# USB.net
KiCad netlist of a schematic drawn in Altium Designer
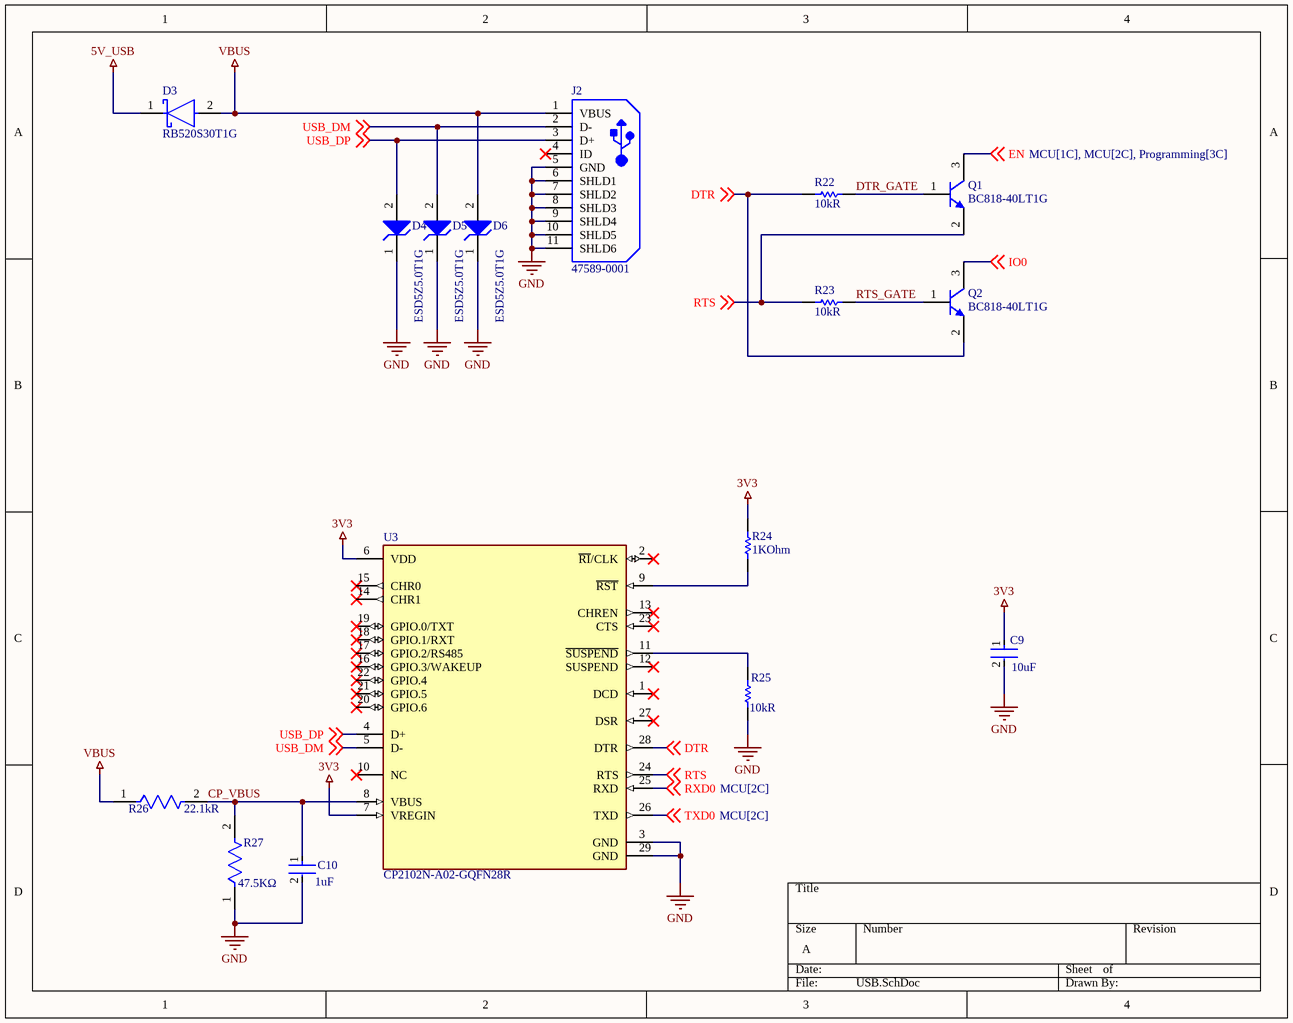
[diagram p0: USB.SchDoc]

(export (version "E")
  (design (tool "Eeschema 10.0.6"))
  (components
    (comp (ref "C9")
      (value "10uF")
      (footprint "FP-C0805C-DG-MFG")
      (description "CAP CER 10UF 10V X5R 0805")
      (fields (field (name "TOLERANCE") "10%") (field (name "MANUFACTURER PART NUMBER") "C0805C106K8PACTU"))
      (libsource (lib "Altium Content Vault") (part "11868f565c42a9108669ba33697ecf6"))
    )
    (comp (ref "C10")
      (value "CL21B105KOFNNNE")
      (footprint "FP-CL21-IPC_A")
      (description "CL21 Series 0805 1uF 16V ±10% Tolerance X7R Multilayer Ceramic Chip Capacitor")
      (fields
        (field (name "CAPACITANCE") "1uF")
        (field (name "TOLERANCE") "10%")
        (field (name "VOLTAGE") "16V")
      )
      (libsource (lib "Altium Content Vault") (part "b4654b650e69147ec39a6b967a45e02"))
    )
    (comp (ref "D3")
      (value "RB520S30T1G")
      (footprint "FP-502-01-MFG")
      (description "DIODE SCHOTTKY 30V 200MA SOD523")
      (libsource (lib "Altium Content Vault") (part "1d6ec82d83fb6aee721767c19dac4b9"))
    )
    (comp (ref "D4")
      (value "ESD5Z5.0T1G")
      (footprint "ONSC-SOD-523-2-502-01_V")
      (fields (field (name "MANUFACTURER") "On Semiconductor"))
      (libsource (lib "Altium Content Vault") (part "ONSC-K1A2-2"))
    )
    (comp (ref "D5")
      (value "ESD5Z5.0T1G")
      (footprint "ONSC-SOD-523-2-502-01_V")
      (fields (field (name "MANUFACTURER") "On Semiconductor"))
      (libsource (lib "Altium Content Vault") (part "ONSC-K1A2-2"))
    )
    (comp (ref "D6")
      (value "ESD5Z5.0T1G")
      (footprint "ONSC-SOD-523-2-502-01_V")
      (fields (field (name "MANUFACTURER") "On Semiconductor"))
      (libsource (lib "Altium Content Vault") (part "ONSC-K1A2-2"))
    )
    (comp (ref "J2")
      (value "47589-0001")
      (footprint "MOLX-47589-0001_V")
      (description "Right Angle Female Type AB Micro USB Connector, 30 V, 1.8 A, -30 to 85 degC, RoHS, Tape and Reel")
      (fields (field (name "MANUFACTURER") "Molex"))
      (libsource (lib "Altium Content Vault") (part "USB-5-6SHLD"))
    )
    (comp (ref "Q1")
      (value "BC818-40LT1G")
      (footprint "ONSC-SOT-23-3-318-08_V")
      (description "General Purpose Transistor, NPN Silicon, 3-Pin SOT-23, Pb-Free, Tape and Reel")
      (fields (field (name "MANUFACTURER") "On Semiconductor"))
      (libsource (lib "Altium Content Vault") (part "ONSC-NPN-B1E2C3-3"))
    )
    (comp (ref "Q2")
      (value "BC818-40LT1G")
      (footprint "ONSC-SOT-23-3-318-08_V")
      (description "General Purpose Transistor, NPN Silicon, 3-Pin SOT-23, Pb-Free, Tape and Reel")
      (fields (field (name "MANUFACTURER") "On Semiconductor"))
      (libsource (lib "Altium Content Vault") (part "ONSC-NPN-B1E2C3-3"))
    )
    (comp (ref "R22")
      (value "10kR")
      (footprint "RESC2013X60X35NL10T20")
      (description "Chip Resistor, 10 KOhm, +/- 1%, 0.125 W, -55 to 155 degC, 0805 (2012 Metric), RoHS, Tape and Reel")
      (fields
        (field (name "MANUFACTURER") "Yageo")
        (field (name "MANUFACTURER PART NUMBER") "RC0805FR-0710KL")
      )
      (libsource (lib "Altium Content Vault") (part "RES-2"))
    )
    (comp (ref "R23")
      (value "10kR")
      (footprint "RESC2013X60X35NL10T20")
      (description "Chip Resistor, 10 KOhm, +/- 1%, 0.125 W, -55 to 155 degC, 0805 (2012 Metric), RoHS, Tape and Reel")
      (fields
        (field (name "MANUFACTURER") "Yageo")
        (field (name "MANUFACTURER PART NUMBER") "RC0805FR-0710KL")
      )
      (libsource (lib "Altium Content Vault") (part "RES-2"))
    )
    (comp (ref "R24")
      (value "RC0805FR-071KL")
      (footprint "RESC2013X60X35ML10T20")
      (description "Chip Resistor, 1 KOhm, +/- 1%, 125 mW, -55 to 155 degC, 0805 (2012 Metric), RoHS, Tape and Reel")
      (fields
        (field (name "RESISTANCE") "1KOhm")
        (field (name "TOLERANCE") "1%")
        (field (name "MANUFACTURER") "Yageo")
      )
      (libsource (lib "Altium Content Vault") (part "RES-2"))
    )
    (comp (ref "R25")
      (value "10kR")
      (footprint "RESC2013X60X35NL10T20")
      (description "Chip Resistor, 10 KOhm, +/- 1%, 0.125 W, -55 to 155 degC, 0805 (2012 Metric), RoHS, Tape and Reel")
      (fields
        (field (name "MANUFACTURER") "Yageo")
        (field (name "MANUFACTURER PART NUMBER") "RC0805FR-0710KL")
      )
      (libsource (lib "Altium Content Vault") (part "RES-2"))
    )
    (comp (ref "R26")
      (value "RMCF0805FT22K1")
      (footprint "FP-RMCF0805-IPC_B")
      (description "22.1kΩ ±1% 0.125W 0805 Thick Film Chip Resistor AEC-Q200 compliant")
      (fields
        (field (name "RESISTANCE") "22.1kR")
        (field (name "TOLERANCE") "1%")
        (field (name "MANUFACTURER") "Stackpole Electronics")
      )
      (libsource (lib "Altium Content Vault") (part "1029c3af85768c4190bb7ad29bc67b5"))
    )
    (comp (ref "R27")
      (value "47.5KΩ")
      (footprint "FP-RN732A-MFG")
      (description "SMD Chip Resistor, Thin Film, 47.5KΩ, 100 V, 0805 [2012 Metric], 100 mW, 0.1%, RN73 Series")
      (fields
        (field (name "MANUFACTURER PART NUMBER") "RN73C2A47K5BTD")
        (field (name "MANUFACTURER") "TE Connectivity")
      )
      (libsource (lib "Altium Content Vault") (part "1029c3af85768c4190bb7ad29bc67b5"))
    )
    (comp (ref "U3")
      (value "CP2102N-A02-GQFN28R")
      (footprint "FP-CP2102N-A02-GQFN28R-MFG")
      (description "IC USB TO UART BRIDGE QFN28")
      (libsource (lib "Altium Content Vault") (part "670edaef084fb69d2a747396d70a05e"))
    )
  )
  (nets
    (net (code "1") (name "/CP_VBUS") (class "Default")
      (node (ref "C10") (pin "1") (pinfunction "1_1") (pintype "passive"))
      (node (ref "R26") (pin "2") (pinfunction "2_2") (pintype "passive"))
      (node (ref "R27") (pin "2") (pinfunction "2_2") (pintype "passive"))
      (node (ref "U3") (pin "8") (pinfunction "VBUS_8") (pintype "input"))
    )
    (net (code "2") (name "/DTR_GATE") (class "Default")
      (node (ref "Q1") (pin "1") (pinfunction "B_1") (pintype "passive"))
      (node (ref "R22") (pin "2") (pinfunction "2_2") (pintype "passive"))
    )
    (net (code "3") (name "/RTS_GATE") (class "Default")
      (node (ref "Q2") (pin "1") (pinfunction "B_1") (pintype "passive"))
      (node (ref "R23") (pin "1") (pinfunction "1_1") (pintype "passive"))
    )
    (net (code "4") (name "3V3") (class "Default")
      (node (ref "C9") (pin "1") (pinfunction "1_1") (pintype "passive"))
      (node (ref "R24") (pin "2") (pinfunction "2_2") (pintype "passive"))
      (node (ref "U3") (pin "6") (pinfunction "VDD_6") (pintype "power_in"))
      (node (ref "U3") (pin "7") (pinfunction "VREGIN_7") (pintype "input"))
    )
    (net (code "5") (name "5V_USB") (class "Default")
      (node (ref "D3") (pin "1") (pinfunction "C_1") (pintype "passive"))
    )
    (net (code "6") (name "DTR") (class "Default")
      (node (ref "Q2") (pin "2") (pinfunction "E_2") (pintype "passive"))
      (node (ref "R22") (pin "1") (pinfunction "1_1") (pintype "passive"))
      (node (ref "U3") (pin "28") (pinfunction "DTR_28") (pintype "output"))
    )
    (net (code "7") (name "EN") (class "Default")
      (node (ref "Q1") (pin "3") (pinfunction "C_3") (pintype "passive"))
    )
    (net (code "8") (name "GND") (class "Default")
      (node (ref "C10") (pin "2") (pinfunction "2_2") (pintype "passive"))
      (node (ref "C9") (pin "2") (pinfunction "2_2") (pintype "passive"))
      (node (ref "D4") (pin "1") (pinfunction "K_1") (pintype "passive"))
      (node (ref "D5") (pin "1") (pinfunction "K_1") (pintype "passive"))
      (node (ref "D6") (pin "1") (pinfunction "K_1") (pintype "passive"))
      (node (ref "J2") (pin "10") (pinfunction "SHLD5_10") (pintype "passive"))
      (node (ref "J2") (pin "11") (pinfunction "SHLD6_11") (pintype "passive"))
      (node (ref "J2") (pin "5") (pinfunction "GND_5") (pintype "passive"))
      (node (ref "J2") (pin "6") (pinfunction "SHLD1_6") (pintype "passive"))
      (node (ref "J2") (pin "7") (pinfunction "SHLD2_7") (pintype "passive"))
      (node (ref "J2") (pin "8") (pinfunction "SHLD3_8") (pintype "passive"))
      (node (ref "J2") (pin "9") (pinfunction "SHLD4_9") (pintype "passive"))
      (node (ref "R25") (pin "1") (pinfunction "1_1") (pintype "passive"))
      (node (ref "R27") (pin "1") (pinfunction "1_1") (pintype "passive"))
      (node (ref "U3") (pin "29") (pinfunction "GND_29") (pintype "power_in"))
      (node (ref "U3") (pin "3") (pinfunction "GND_3") (pintype "power_in"))
    )
    (net (code "9") (name "IO0") (class "Default")
      (node (ref "Q2") (pin "3") (pinfunction "C_3") (pintype "passive"))
    )
    (net (code "10") (name "Net-(U3-~{RST})") (class "Default")
      (node (ref "R24") (pin "1") (pinfunction "1_1") (pintype "passive"))
      (node (ref "U3") (pin "9") (pinfunction "~{RST}_9") (pintype "input"))
    )
    (net (code "11") (name "Net-(U3-~{SUSPEND})") (class "Default")
      (node (ref "R25") (pin "2") (pinfunction "2_2") (pintype "passive"))
      (node (ref "U3") (pin "11") (pinfunction "~{SUSPEND}_11") (pintype "output"))
    )
    (net (code "12") (name "RTS") (class "Default")
      (node (ref "Q1") (pin "2") (pinfunction "E_2") (pintype "passive"))
      (node (ref "R23") (pin "2") (pinfunction "2_2") (pintype "passive"))
      (node (ref "U3") (pin "24") (pinfunction "RTS_24") (pintype "output"))
    )
    (net (code "13") (name "RXD0") (class "Default")
      (node (ref "U3") (pin "25") (pinfunction "RXD_25") (pintype "input"))
    )
    (net (code "14") (name "TXD0") (class "Default")
      (node (ref "U3") (pin "26") (pinfunction "TXD_26") (pintype "output"))
    )
    (net (code "15") (name "USB_DM") (class "Default")
      (node (ref "D5") (pin "2") (pinfunction "A_2") (pintype "passive"))
      (node (ref "J2") (pin "2") (pinfunction "D-_2") (pintype "passive"))
      (node (ref "U3") (pin "5") (pinfunction "D-_5") (pintype "passive"))
    )
    (net (code "16") (name "USB_DP") (class "Default")
      (node (ref "D4") (pin "2") (pinfunction "A_2") (pintype "passive"))
      (node (ref "J2") (pin "3") (pinfunction "D+_3") (pintype "passive"))
      (node (ref "U3") (pin "4") (pinfunction "D+_4") (pintype "passive"))
    )
    (net (code "17") (name "VBUS") (class "Default")
      (node (ref "D3") (pin "2") (pinfunction "A_2") (pintype "passive"))
      (node (ref "D6") (pin "2") (pinfunction "A_2") (pintype "passive"))
      (node (ref "J2") (pin "1") (pinfunction "VBUS_1") (pintype "passive"))
      (node (ref "R26") (pin "1") (pinfunction "1_1") (pintype "passive"))
    )
    (net (code "18") (name "unconnected-(J2-ID-Pad4)") (class "Default")
      (node (ref "J2") (pin "4") (pinfunction "ID_4") (pintype "passive+no_connect"))
    )
    (net (code "19") (name "unconnected-(U3-CHR0-Pad15)") (class "Default")
      (node (ref "U3") (pin "15") (pinfunction "CHR0_15") (pintype "output+no_connect"))
    )
    (net (code "20") (name "unconnected-(U3-CHR1-Pad14)") (class "Default")
      (node (ref "U3") (pin "14") (pinfunction "CHR1_14") (pintype "output+no_connect"))
    )
    (net (code "21") (name "unconnected-(U3-CHREN-Pad13)") (class "Default")
      (node (ref "U3") (pin "13") (pinfunction "CHREN_13") (pintype "output+no_connect"))
    )
    (net (code "22") (name "unconnected-(U3-CTS-Pad23)") (class "Default")
      (node (ref "U3") (pin "23") (pinfunction "CTS_23") (pintype "input+no_connect"))
    )
    (net (code "23") (name "unconnected-(U3-DCD-Pad1)") (class "Default")
      (node (ref "U3") (pin "1") (pinfunction "DCD_1") (pintype "input+no_connect"))
    )
    (net (code "24") (name "unconnected-(U3-DSR-Pad27)") (class "Default")
      (node (ref "U3") (pin "27") (pinfunction "DSR_27") (pintype "input+no_connect"))
    )
    (net (code "25") (name "unconnected-(U3-GPIO.0{slash}TXT-Pad19)") (class "Default")
      (node (ref "U3") (pin "19") (pinfunction "GPIO.0/TXT_19") (pintype "bidirectional+no_connect"))
    )
    (net (code "26") (name "unconnected-(U3-GPIO.1{slash}RXT-Pad18)") (class "Default")
      (node (ref "U3") (pin "18") (pinfunction "GPIO.1/RXT_18") (pintype "bidirectional+no_connect"))
    )
    (net (code "27") (name "unconnected-(U3-GPIO.2{slash}RS485-Pad17)") (class "Default")
      (node (ref "U3") (pin "17") (pinfunction "GPIO.2/RS485_17") (pintype "bidirectional+no_connect"))
    )
    (net (code "28") (name "unconnected-(U3-GPIO.3{slash}WAKEUP-Pad16)") (class "Default")
      (node (ref "U3") (pin "16") (pinfunction "GPIO.3/WAKEUP_16") (pintype "bidirectional+no_connect"))
    )
    (net (code "29") (name "unconnected-(U3-GPIO.4-Pad22)") (class "Default")
      (node (ref "U3") (pin "22") (pinfunction "GPIO.4_22") (pintype "bidirectional+no_connect"))
    )
    (net (code "30") (name "unconnected-(U3-GPIO.5-Pad21)") (class "Default")
      (node (ref "U3") (pin "21") (pinfunction "GPIO.5_21") (pintype "bidirectional+no_connect"))
    )
    (net (code "31") (name "unconnected-(U3-GPIO.6-Pad20)") (class "Default")
      (node (ref "U3") (pin "20") (pinfunction "GPIO.6_20") (pintype "bidirectional+no_connect"))
    )
    (net (code "32") (name "unconnected-(U3-NC-Pad10)") (class "Default")
      (node (ref "U3") (pin "10") (pinfunction "NC_10") (pintype "passive+no_connect"))
    )
    (net (code "33") (name "unconnected-(U3-SUSPEND-Pad12)") (class "Default")
      (node (ref "U3") (pin "12") (pinfunction "SUSPEND_12") (pintype "output+no_connect"))
    )
    (net (code "34") (name "unconnected-(U3-~{RI}{slash}CLK-Pad2)") (class "Default")
      (node (ref "U3") (pin "2") (pinfunction "~{RI}/CLK_2") (pintype "bidirectional+no_connect"))
    )
  )
)
